# prosthesis.net
KiCad netlist of a schematic drawn in Altium Designer
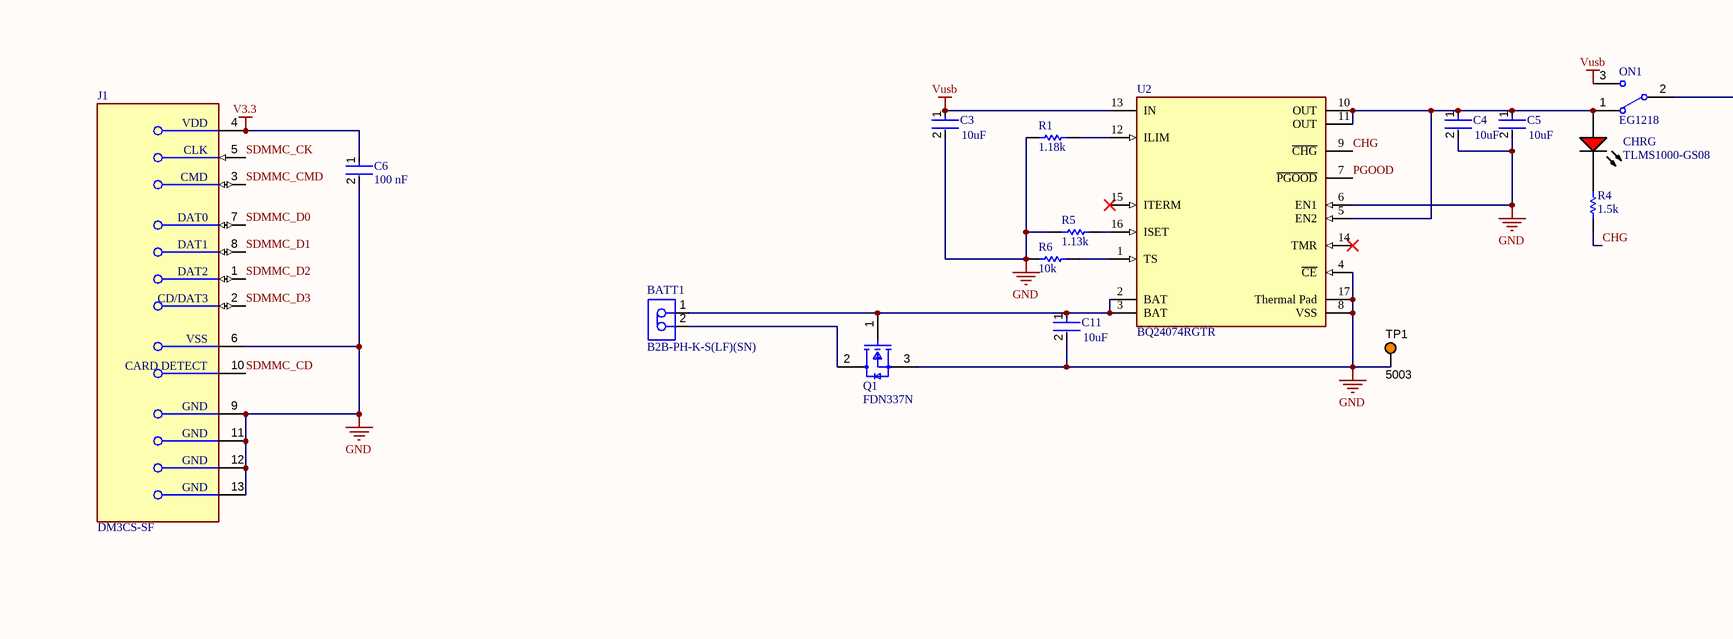
[diagram p0: prosthesis.SchDoc, top left]
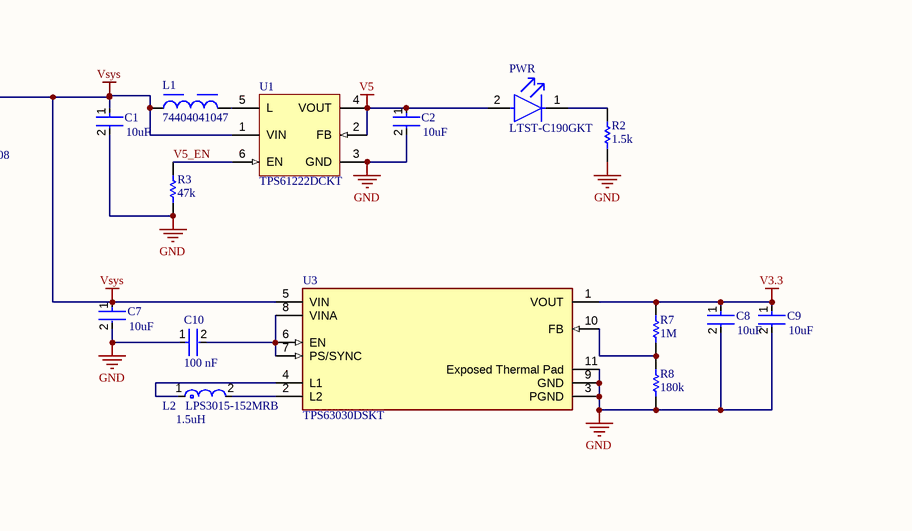
[diagram p1: prosthesis.SchDoc, top right]
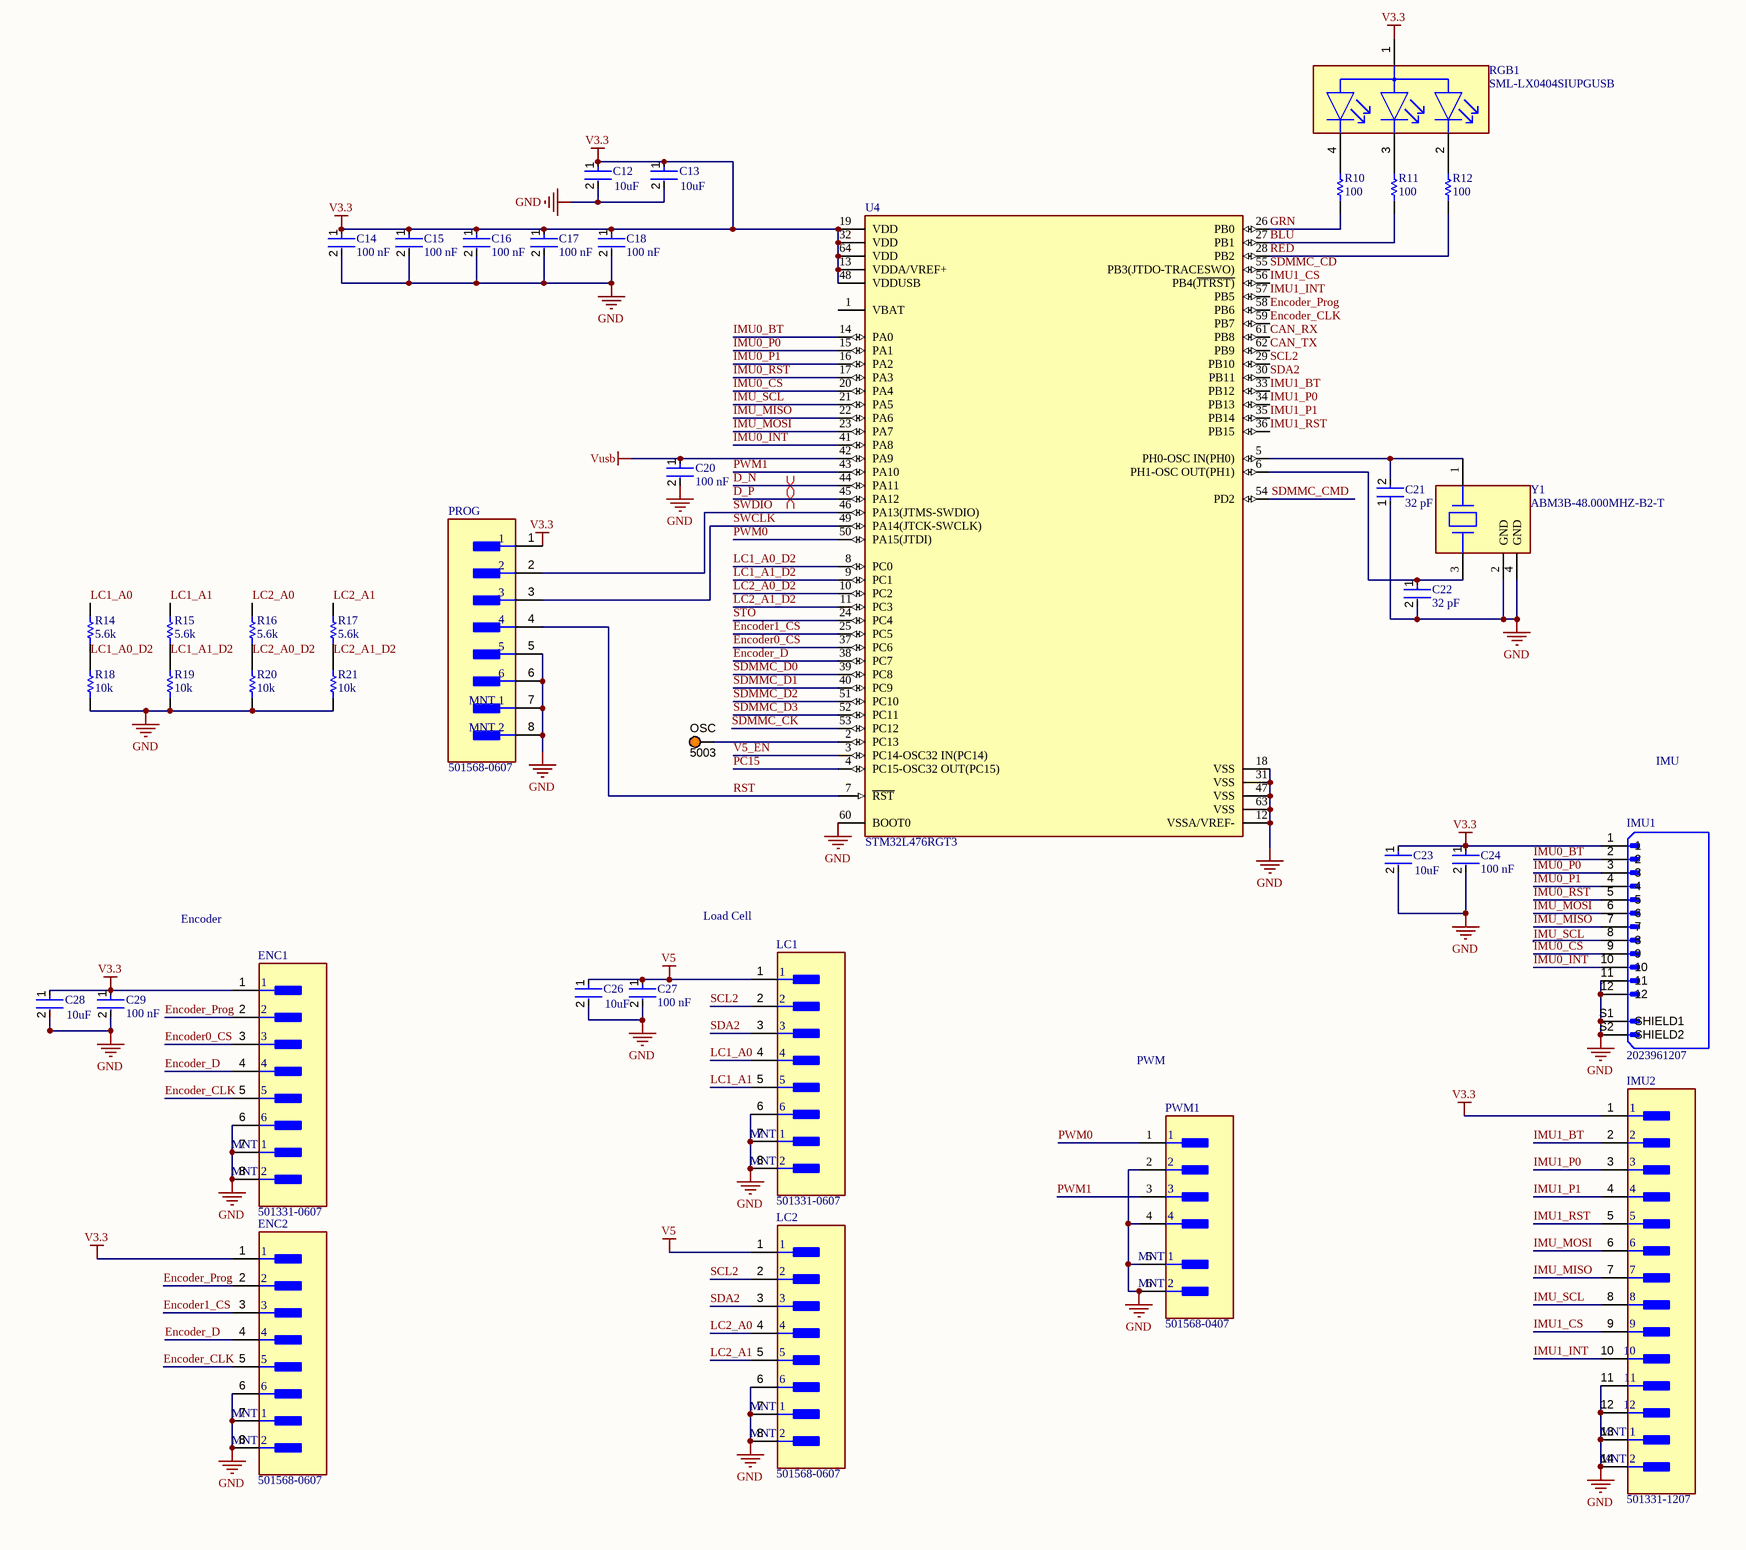
[diagram p2: prosthesis.SchDoc, bottom left]
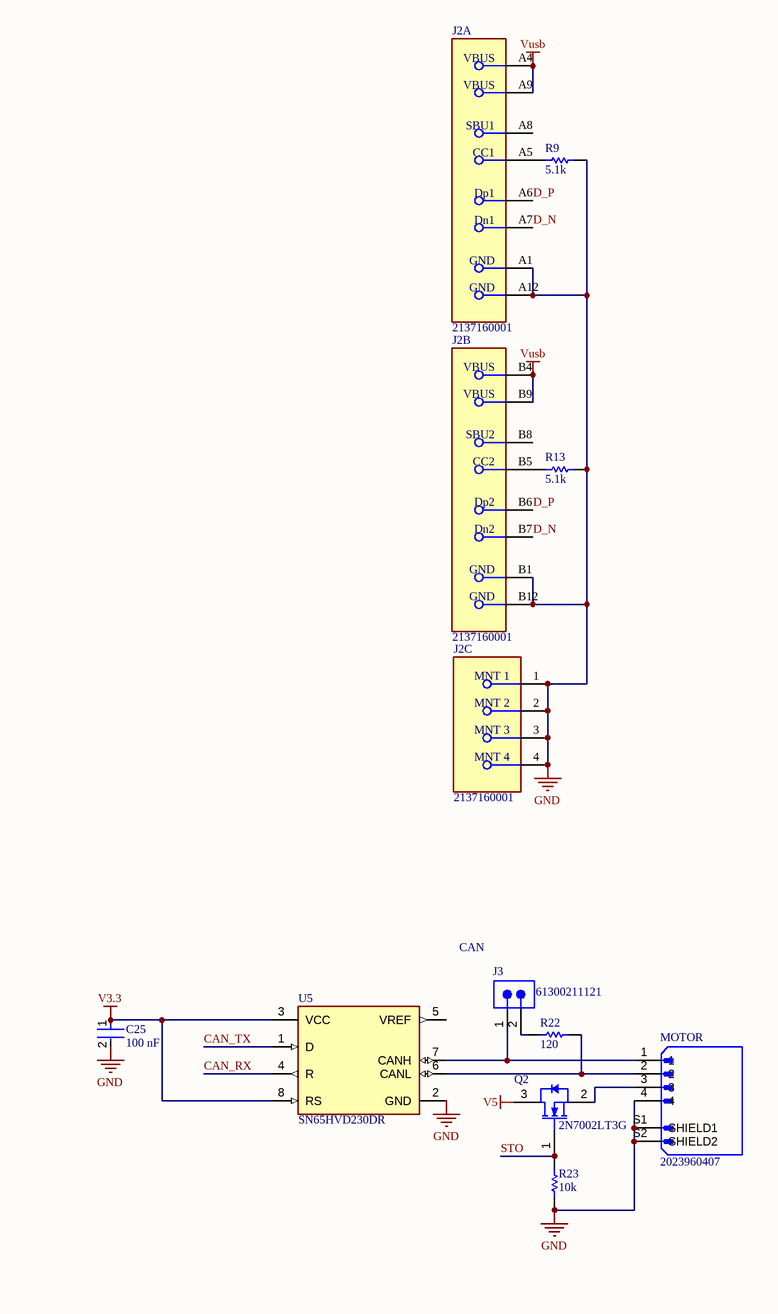
[diagram p3: prosthesis.SchDoc, bottom right]

(export (version "E")
  (design (tool "Eeschema 10.0.6"))
  (components
    (comp (ref "BATT1")
      (value "B2B-PH-K-S(LF)(SN)")
      (footprint "JST-B2B-PH-K-S_V")
      (fields (field (name "MANUFACTURER") "JST"))
      (libsource (lib "Altium Content Vault") (part "CN-2P-F-QF2"))
    )
    (comp (ref "C1")
      (value "GRM21BR61C106KE15L")
      (footprint "FP-GRM21B-0_1-IPC_C")
      (description "Chip Multilayer Ceramic Capacitors for General Purpose, 0805, 10uF, X5R, 15%, 10%, 16V")
      (fields
        (field (name "TOLERANCE") "10%")
        (field (name "VOLTAGE") "16V")
        (field (name "CAPACITANCE") "10uF")
      )
      (libsource (lib "Altium Content Vault") (part "b4654b650e69147ec39a6b967a45e02"))
    )
    (comp (ref "C2")
      (value "GRM21BR61C106KE15L")
      (footprint "FP-GRM21B-0_1-IPC_C")
      (description "Chip Multilayer Ceramic Capacitors for General Purpose, 0805, 10uF, X5R, 15%, 10%, 16V")
      (fields
        (field (name "TOLERANCE") "10%")
        (field (name "VOLTAGE") "16V")
        (field (name "CAPACITANCE") "10uF")
      )
      (libsource (lib "Altium Content Vault") (part "b4654b650e69147ec39a6b967a45e02"))
    )
    (comp (ref "C3")
      (value "GRM21BR61C106KE15L")
      (footprint "FP-GRM21B-0_1-IPC_C")
      (description "Chip Multilayer Ceramic Capacitors for General Purpose, 0805, 10uF, X5R, 15%, 10%, 16V")
      (fields
        (field (name "TOLERANCE") "10%")
        (field (name "VOLTAGE") "16V")
        (field (name "CAPACITANCE") "10uF")
      )
      (libsource (lib "Altium Content Vault") (part "b4654b650e69147ec39a6b967a45e02"))
    )
    (comp (ref "C4")
      (value "GRM21BR61C106KE15L")
      (footprint "FP-GRM21B-0_1-IPC_C")
      (description "Chip Multilayer Ceramic Capacitors for General Purpose, 0805, 10uF, X5R, 15%, 10%, 16V")
      (fields
        (field (name "TOLERANCE") "10%")
        (field (name "VOLTAGE") "16V")
        (field (name "CAPACITANCE") "10uF")
      )
      (libsource (lib "Altium Content Vault") (part "b4654b650e69147ec39a6b967a45e02"))
    )
    (comp (ref "C5")
      (value "GRM21BR61C106KE15L")
      (footprint "FP-GRM21B-0_1-IPC_C")
      (description "Chip Multilayer Ceramic Capacitors for General Purpose, 0805, 10uF, X5R, 15%, 10%, 16V")
      (fields
        (field (name "TOLERANCE") "10%")
        (field (name "VOLTAGE") "16V")
        (field (name "CAPACITANCE") "10uF")
      )
      (libsource (lib "Altium Content Vault") (part "b4654b650e69147ec39a6b967a45e02"))
    )
    (comp (ref "C6")
      (value "100 nF")
      (footprint "FP-CC0805-0_85-MFG")
      (description "CAP CER 0.1UF 16V X7R 0805")
      (fields
        (field (name "MANUFACTURER PART NUMBER") "CC0805KRX7R7BB104")
        (field (name "MANUFACTURER") "Yageo")
      )
      (libsource (lib "Altium Content Vault") (part "11868f565c42a9108669ba33697ecf6"))
    )
    (comp (ref "C7")
      (value "GRM21BR61C106KE15L")
      (footprint "FP-GRM21B-0_1-IPC_C")
      (description "Chip Multilayer Ceramic Capacitors for General Purpose, 0805, 10uF, X5R, 15%, 10%, 16V")
      (fields
        (field (name "TOLERANCE") "10%")
        (field (name "VOLTAGE") "16V")
        (field (name "CAPACITANCE") "10uF")
      )
      (libsource (lib "Altium Content Vault") (part "b4654b650e69147ec39a6b967a45e02"))
    )
    (comp (ref "C8")
      (value "GRM21BR61C106KE15L")
      (footprint "FP-GRM21B-0_1-IPC_C")
      (description "Chip Multilayer Ceramic Capacitors for General Purpose, 0805, 10uF, X5R, 15%, 10%, 16V")
      (fields
        (field (name "TOLERANCE") "10%")
        (field (name "VOLTAGE") "16V")
        (field (name "CAPACITANCE") "10uF")
      )
      (libsource (lib "Altium Content Vault") (part "b4654b650e69147ec39a6b967a45e02"))
    )
    (comp (ref "C9")
      (value "GRM21BR61C106KE15L")
      (footprint "FP-GRM21B-0_1-IPC_C")
      (description "Chip Multilayer Ceramic Capacitors for General Purpose, 0805, 10uF, X5R, 15%, 10%, 16V")
      (fields
        (field (name "TOLERANCE") "10%")
        (field (name "VOLTAGE") "16V")
        (field (name "CAPACITANCE") "10uF")
      )
      (libsource (lib "Altium Content Vault") (part "b4654b650e69147ec39a6b967a45e02"))
    )
    (comp (ref "C10")
      (value "100 nF")
      (footprint "FP-CC0805-0_85-MFG")
      (description "CAP CER 0.1UF 16V X7R 0805")
      (fields
        (field (name "MANUFACTURER PART NUMBER") "CC0805KRX7R7BB104")
        (field (name "MANUFACTURER") "Yageo")
      )
      (libsource (lib "Altium Content Vault") (part "11868f565c42a9108669ba33697ecf6"))
    )
    (comp (ref "C11")
      (value "GRM21BR61C106KE15L")
      (footprint "FP-GRM21B-0_1-IPC_C")
      (description "Chip Multilayer Ceramic Capacitors for General Purpose, 0805, 10uF, X5R, 15%, 10%, 16V")
      (fields
        (field (name "TOLERANCE") "10%")
        (field (name "VOLTAGE") "16V")
        (field (name "CAPACITANCE") "10uF")
      )
      (libsource (lib "Altium Content Vault") (part "b4654b650e69147ec39a6b967a45e02"))
    )
    (comp (ref "C12")
      (value "GRM21BR61C106KE15L")
      (footprint "FP-GRM21B-0_1-IPC_C")
      (description "Chip Multilayer Ceramic Capacitors for General Purpose, 0805, 10uF, X5R, 15%, 10%, 16V")
      (fields
        (field (name "TOLERANCE") "10%")
        (field (name "VOLTAGE") "16V")
        (field (name "CAPACITANCE") "10uF")
      )
      (libsource (lib "Altium Content Vault") (part "b4654b650e69147ec39a6b967a45e02"))
    )
    (comp (ref "C13")
      (value "GRM21BR61C106KE15L")
      (footprint "FP-GRM21B-0_1-IPC_C")
      (description "Chip Multilayer Ceramic Capacitors for General Purpose, 0805, 10uF, X5R, 15%, 10%, 16V")
      (fields
        (field (name "TOLERANCE") "10%")
        (field (name "VOLTAGE") "16V")
        (field (name "CAPACITANCE") "10uF")
      )
      (libsource (lib "Altium Content Vault") (part "b4654b650e69147ec39a6b967a45e02"))
    )
    (comp (ref "C14")
      (value "100 nF")
      (footprint "FP-CC0805-0_85-MFG")
      (description "CAP CER 0.1UF 16V X7R 0805")
      (fields
        (field (name "MANUFACTURER PART NUMBER") "CC0805KRX7R7BB104")
        (field (name "MANUFACTURER") "Yageo")
      )
      (libsource (lib "Altium Content Vault") (part "11868f565c42a9108669ba33697ecf6"))
    )
    (comp (ref "C15")
      (value "100 nF")
      (footprint "FP-CC0805-0_85-MFG")
      (description "CAP CER 0.1UF 16V X7R 0805")
      (fields
        (field (name "MANUFACTURER PART NUMBER") "CC0805KRX7R7BB104")
        (field (name "MANUFACTURER") "Yageo")
      )
      (libsource (lib "Altium Content Vault") (part "11868f565c42a9108669ba33697ecf6"))
    )
    (comp (ref "C16")
      (value "100 nF")
      (footprint "FP-CC0805-0_85-MFG")
      (description "CAP CER 0.1UF 16V X7R 0805")
      (fields
        (field (name "MANUFACTURER PART NUMBER") "CC0805KRX7R7BB104")
        (field (name "MANUFACTURER") "Yageo")
      )
      (libsource (lib "Altium Content Vault") (part "11868f565c42a9108669ba33697ecf6"))
    )
    (comp (ref "C17")
      (value "100 nF")
      (footprint "FP-CC0805-0_85-MFG")
      (description "CAP CER 0.1UF 16V X7R 0805")
      (fields
        (field (name "MANUFACTURER PART NUMBER") "CC0805KRX7R7BB104")
        (field (name "MANUFACTURER") "Yageo")
      )
      (libsource (lib "Altium Content Vault") (part "11868f565c42a9108669ba33697ecf6"))
    )
    (comp (ref "C18")
      (value "100 nF")
      (footprint "FP-CC0805-0_85-MFG")
      (description "CAP CER 0.1UF 16V X7R 0805")
      (fields
        (field (name "MANUFACTURER PART NUMBER") "CC0805KRX7R7BB104")
        (field (name "MANUFACTURER") "Yageo")
      )
      (libsource (lib "Altium Content Vault") (part "11868f565c42a9108669ba33697ecf6"))
    )
    (comp (ref "C20")
      (value "100 nF")
      (footprint "FP-CC0805-0_85-MFG")
      (description "CAP CER 0.1UF 16V X7R 0805")
      (fields
        (field (name "MANUFACTURER PART NUMBER") "CC0805KRX7R7BB104")
        (field (name "MANUFACTURER") "Yageo")
      )
      (libsource (lib "Altium Content Vault") (part "11868f565c42a9108669ba33697ecf6"))
    )
    (comp (ref "C21")
      (value "32 pF")
      (footprint "FP-CC0805-0_85-MFG")
      (description "CAP CER 32pF 16V X7R 0805")
      (fields
        (field (name "MANUFACTURER PART NUMBER") "CC0805KRX7R7BB104")
        (field (name "MANUFACTURER") "Yageo")
      )
      (libsource (lib "Altium Content Vault") (part "11868f565c42a9108669ba33697ecf6"))
    )
    (comp (ref "C22")
      (value "32 pF")
      (footprint "FP-CC0805-0_85-MFG")
      (description "CAP CER 32pF 16V X7R 0805")
      (fields
        (field (name "MANUFACTURER PART NUMBER") "CC0805KRX7R7BB104")
        (field (name "MANUFACTURER") "Yageo")
      )
      (libsource (lib "Altium Content Vault") (part "11868f565c42a9108669ba33697ecf6"))
    )
    (comp (ref "C23")
      (value "GRM21BR61C106KE15L")
      (footprint "FP-GRM21B-0_1-IPC_C")
      (description "Chip Multilayer Ceramic Capacitors for General Purpose, 0805, 10uF, X5R, 15%, 10%, 16V")
      (fields
        (field (name "TOLERANCE") "10%")
        (field (name "VOLTAGE") "16V")
        (field (name "CAPACITANCE") "10uF")
      )
      (libsource (lib "Altium Content Vault") (part "b4654b650e69147ec39a6b967a45e02"))
    )
    (comp (ref "C24")
      (value "100 nF")
      (footprint "FP-CC0805-0_85-MFG")
      (description "CAP CER 0.1UF 16V X7R 0805")
      (fields
        (field (name "MANUFACTURER PART NUMBER") "CC0805KRX7R7BB104")
        (field (name "MANUFACTURER") "Yageo")
      )
      (libsource (lib "Altium Content Vault") (part "11868f565c42a9108669ba33697ecf6"))
    )
    (comp (ref "C25")
      (value "100 nF")
      (footprint "FP-CC0805-0_85-MFG")
      (description "CAP CER 0.1UF 16V X7R 0805")
      (fields
        (field (name "MANUFACTURER PART NUMBER") "CC0805KRX7R7BB104")
        (field (name "MANUFACTURER") "Yageo")
      )
      (libsource (lib "Altium Content Vault") (part "11868f565c42a9108669ba33697ecf6"))
    )
    (comp (ref "C26")
      (value "GRM21BR61C106KE15L")
      (footprint "FP-GRM21B-0_1-IPC_C")
      (description "Chip Multilayer Ceramic Capacitors for General Purpose, 0805, 10uF, X5R, 15%, 10%, 16V")
      (fields
        (field (name "TOLERANCE") "10%")
        (field (name "VOLTAGE") "16V")
        (field (name "CAPACITANCE") "10uF")
      )
      (libsource (lib "Altium Content Vault") (part "b4654b650e69147ec39a6b967a45e02"))
    )
    (comp (ref "C27")
      (value "100 nF")
      (footprint "FP-CC0805-0_85-MFG")
      (description "CAP CER 0.1UF 16V X7R 0805")
      (fields
        (field (name "MANUFACTURER PART NUMBER") "CC0805KRX7R7BB104")
        (field (name "MANUFACTURER") "Yageo")
      )
      (libsource (lib "Altium Content Vault") (part "11868f565c42a9108669ba33697ecf6"))
    )
    (comp (ref "C28")
      (value "GRM21BR61C106KE15L")
      (footprint "FP-GRM21B-0_1-IPC_C")
      (description "Chip Multilayer Ceramic Capacitors for General Purpose, 0805, 10uF, X5R, 15%, 10%, 16V")
      (fields
        (field (name "TOLERANCE") "10%")
        (field (name "VOLTAGE") "16V")
        (field (name "CAPACITANCE") "10uF")
      )
      (libsource (lib "Altium Content Vault") (part "b4654b650e69147ec39a6b967a45e02"))
    )
    (comp (ref "C29")
      (value "100 nF")
      (footprint "FP-CC0805-0_85-MFG")
      (description "CAP CER 0.1UF 16V X7R 0805")
      (fields
        (field (name "MANUFACTURER PART NUMBER") "CC0805KRX7R7BB104")
        (field (name "MANUFACTURER") "Yageo")
      )
      (libsource (lib "Altium Content Vault") (part "11868f565c42a9108669ba33697ecf6"))
    )
    (comp (ref "CHRG")
      (value "TLMS1000-GS08")
      (footprint "VISH-TLMS1000_V")
      (description "Low Current LED, 40 mW, 1.8 V, -40 to 100 degC, 2-Pin SMD (0603), RoHS, Tape and Reel")
      (fields (field (name "MANUFACTURER") "Vishay"))
      (libsource (lib "Altium Content Vault") (part "LED-RED-AK-2"))
    )
    (comp (ref "ENC1")
      (value "501331-0607")
      (footprint "FP-501331-0607-MFG")
      (description "CONN HEADER SMD 6POS 1MM")
      (libsource (lib "Altium Content Vault") (part "2bd7785e6f3406c6201afa29ba70f07"))
    )
    (comp (ref "ENC2")
      (value "501568-0607")
      (footprint "FP-501568-0607-MFG")
      (description "CONN HEADER SMD R/A 6POS 1MM")
      (fields
        (field (name "MANUFACTURER") "Molex")
        (field (name "OCTOPART") "https://octopart.com/501568-0607-molex-1389391")
      )
      (libsource (lib "") (part "1b394f14087da03cce32c17bd8f6206_1"))
    )
    (comp (ref "IMU1")
      (value "2023961207")
      (footprint "MOLEX_2023961207")
      (libsource (lib "2023961207") (part "2023961207"))
    )
    (comp (ref "IMU2")
      (value "501331-1207")
      (footprint "FP-501331-1207-MFG")
      (description "CONN HEADER SMD 12POS 1MM")
      (libsource (lib "Altium Content Vault") (part "17576ad8f6f7a90bfd1824352d618be"))
    )
    (comp (ref "J1")
      (value "DM3CS-SF")
      (footprint "FP-DM3CS-SF-MFG")
      (description "CONN MICRO SD CARD HINGED TYPE")
      (libsource (lib "Altium Content Vault") (part "bac915de5305cfdd1ca301aae530106"))
    )
    (comp (ref "J2")
      (value "2137160001")
      (footprint "FP-2137160001-MFG")
      (description "2137160001 Conn USB 2.0 Type C F 16 POS 0.85mm Solder RA Thru-Hole 16 Terminal 1 Port T/R")
      (libsource (lib "Altium Content Vault") (part "b696ed38c1c45f0dfa1e84b6b439290"))
    )
    (comp (ref "J3")
      (value "61300211121")
      (footprint "61300211121")
      (libsource (lib "Altium Content Vault") (part "Header_Male_1R_02P"))
    )
    (comp (ref "L1")
      (value "74404041047")
      (footprint "WE-LQS_4012")
      (description "74404041047 Inductors, Fixed, WE-LQS SMD 4012 4.7uH 1.55A 91mOhms")
      (fields (field (name "TOLERANCE") "20%"))
      (libsource (lib "Altium Content Vault") (part "Inductor - 3"))
    )
    (comp (ref "L2")
      (value "LPS3015-152MRB")
      (footprint "FP-LPS3015-MFG")
      (description "Fixed Inductors LPS3015 AEC-Q200 1.5uH 1.4A 20% SMD")
      (fields (field (name "INDUCTANCE") "1.5uH") (field (name "TOLERANCE") "20%"))
      (libsource (lib "Altium Content Vault") (part "4cc4b267dca4c8e51f7102f422741d8"))
    )
    (comp (ref "LC1")
      (value "501331-0607")
      (footprint "FP-501331-0607-MFG")
      (description "CONN HEADER SMD 6POS 1MM")
      (libsource (lib "Altium Content Vault") (part "2bd7785e6f3406c6201afa29ba70f07"))
    )
    (comp (ref "LC2")
      (value "501568-0607")
      (footprint "FP-501568-0607-MFG")
      (description "CONN HEADER SMD R/A 6POS 1MM")
      (fields
        (field (name "MANUFACTURER") "Molex")
        (field (name "OCTOPART") "https://octopart.com/501568-0607-molex-1389391")
      )
      (libsource (lib "") (part "1b394f14087da03cce32c17bd8f6206_1"))
    )
    (comp (ref "MOTOR")
      (value "2023960407")
      (footprint "MOLEX_2023960407")
      (libsource (lib "2023960407") (part "2023960407"))
    )
    (comp (ref "ON1")
      (value "EG1218")
      (footprint "ESWI-EG1218_V")
      (description "Slide Switch, 500 V, -20 to 70 degC, 3-Pin THD, RoHS")
      (libsource (lib "Altium Content Vault") (part "SW-SPDT-3_B"))
    )
    (comp (ref "OSC")
      (value "5003")
      (footprint "KSTN-5003")
      (description "Test Point, Orange, 1-Pin THD, RoHS")
      (libsource (lib "Altium Content Vault") (part "TESTPOINT_ORANGE"))
    )
    (comp (ref "PROG")
      (value "501568-0607")
      (footprint "FP-501568-0607-MFG")
      (description "CONN HEADER SMD R/A 6POS 1MM")
      (fields
        (field (name "MANUFACTURER") "Molex")
        (field (name "OCTOPART") "https://octopart.com/501568-0607-molex-1389391")
      )
      (libsource (lib "Altium Content Vault") (part "1b394f14087da03cce32c17bd8f6206"))
    )
    (comp (ref "PWM1")
      (value "501568-0407")
      (footprint "FP-501568-0407-MFG")
      (description "CONN HEADER SMD R/A 4POS 1MM")
      (libsource (lib "Altium Content Vault") (part "9ad138ae26d927171cc05ac156b0a09"))
    )
    (comp (ref "PWR")
      (value "LTST-C190GKT")
      (footprint "FP-LTST-C190GKT-MFG")
      (description "LED GREEN CLEAR CHIP SMD")
      (fields (field (name "VOLTAGE") "2V"))
      (libsource (lib "Altium Content Vault") (part "8706943c75ba83719d021d2fdc84c58"))
    )
    (comp (ref "Q1")
      (value "FDN337N")
      (footprint "FP-527AG-MFG")
      (description "MOSFET N-CH 30V 2.2A SSOT3")
      (libsource (lib "Altium Content Vault") (part "b44c8776e10362b01251f5cff19d373"))
    )
    (comp (ref "Q2")
      (value "2N7002LT3G")
      (footprint "ONSC-SOT-23-3-318-08_V")
      (description "Small Signal MOSFET, 60 V, 115 mA, N-Channel, 3-Pin SOT-23, Pb-Free, Tape and Reel")
      (fields (field (name "MANUFACTURER") "On Semiconductor"))
      (libsource (lib "Altium Content Vault") (part "ONSC-NMOS-G1S2D3-3"))
    )
    (comp (ref "R1")
      (value "1.18k")
      (footprint "RESC2013X70X40ML20T20")
      (fields (field (name "MANUFACTURER") "Panasonic") (field (name "PART NUMBER") "ERJ-6ENF1181V"))
      (libsource (lib "Altium Content Vault") (part "RES"))
    )
    (comp (ref "R2")
      (value "1.5k")
      (footprint "RESC2013X70X40NL20T20")
      (fields (field (name "MANUFACTURER") "Panasonic") (field (name "PART NUMBER") "ERJ-6GEYJ152V"))
      (libsource (lib "Altium Content Vault") (part "RES"))
    )
    (comp (ref "R3")
      (value "47k")
      (footprint "RESC2013X70X40ML20T20")
      (fields (field (name "MANUFACTURER") "Panasonic") (field (name "PART NUMBER") "ERJ-6GEYJ473V"))
      (libsource (lib "Altium Content Vault") (part "RES"))
    )
    (comp (ref "R4")
      (value "1.5k")
      (footprint "RESC2013X70X40NL20T20")
      (fields (field (name "MANUFACTURER") "Panasonic") (field (name "PART NUMBER") "ERJ-6GEYJ152V"))
      (libsource (lib "Altium Content Vault") (part "RES"))
    )
    (comp (ref "R5")
      (value "1.13k")
      (footprint "RESC2013X60X35NL10T20")
      (fields (field (name "MANUFACTURER") "Yageo") (field (name "PART NUMBER") "RC0805FR-071K13L"))
      (libsource (lib "Altium Content Vault") (part "RES"))
    )
    (comp (ref "R6")
      (value "10k")
      (footprint "RESC2013X60X35NL10T20")
      (description "Chip Resistor, 10 KOhm, +/- 1%, 0.125 W, -55 to 155 degC, 0805 (2012 Metric), RoHS, Tape and Reel")
      (fields (field (name "MANUFACTURER") "Yageo"))
      (libsource (lib "Altium Content Vault") (part "RES-2"))
    )
    (comp (ref "R7")
      (value "1M")
      (footprint "RESC1608X55X30NL15T15")
      (fields (field (name "PART NUMBER") "ERJ-3GEYJ105V") (field (name "MANUFACTURER") "Panasonic"))
      (libsource (lib "Altium Content Vault") (part "RES"))
    )
    (comp (ref "R8")
      (value "180k")
      (footprint "RESC2013X50X40NL20T20")
      (fields (field (name "PART NUMBER") "RG2012N-184-W-T1") (field (name "MANUFACTURER") "Susumu"))
      (libsource (lib "Altium Content Vault") (part "RES"))
    )
    (comp (ref "R9")
      (value "5.1k")
      (footprint "RESC2013X60X40LL20T25")
      (fields (field (name "MANUFACTURER") "Panasonic") (field (name "PART NUMBER") "ERA-6YEB512V"))
      (libsource (lib "Altium Content Vault") (part "RES"))
    )
    (comp (ref "R10")
      (value "100")
      (footprint "RESC2013X60X40ML20T25")
      (fields (field (name "MANUFACTURER") "Panasonic") (field (name "PART NUMBER") "ERA6AEB101V"))
      (libsource (lib "Altium Content Vault") (part "RES"))
    )
    (comp (ref "R11")
      (value "100")
      (footprint "RESC2013X60X40ML20T25")
      (fields (field (name "MANUFACTURER") "Panasonic") (field (name "PART NUMBER") "ERA6AEB101V"))
      (libsource (lib "Altium Content Vault") (part "RES"))
    )
    (comp (ref "R12")
      (value "100")
      (footprint "RESC2013X60X40ML20T25")
      (fields (field (name "MANUFACTURER") "Panasonic") (field (name "PART NUMBER") "ERA6AEB101V"))
      (libsource (lib "Altium Content Vault") (part "RES"))
    )
    (comp (ref "R13")
      (value "5.1k")
      (footprint "RESC2013X60X40LL20T25")
      (fields (field (name "MANUFACTURER") "Panasonic") (field (name "PART NUMBER") "ERA-6YEB512V"))
      (libsource (lib "Altium Content Vault") (part "RES"))
    )
    (comp (ref "R14")
      (value "5.6k")
      (footprint "RESC2013X70X40LL20T20")
      (fields (field (name "PART NUMBER") "ERJ6ENF5601V") (field (name "MANUFACTURER") "Panasonic"))
      (libsource (lib "Altium Content Vault") (part "RES"))
    )
    (comp (ref "R15")
      (value "5.6k")
      (footprint "RESC2013X70X40LL20T20")
      (fields (field (name "PART NUMBER") "ERJ6ENF5601V") (field (name "MANUFACTURER") "Panasonic"))
      (libsource (lib "Altium Content Vault") (part "RES"))
    )
    (comp (ref "R16")
      (value "5.6k")
      (footprint "RESC2013X70X40LL20T20")
      (fields (field (name "PART NUMBER") "ERJ6ENF5601V") (field (name "MANUFACTURER") "Panasonic"))
      (libsource (lib "Altium Content Vault") (part "RES"))
    )
    (comp (ref "R17")
      (value "5.6k")
      (footprint "RESC2013X70X40LL20T20")
      (fields (field (name "PART NUMBER") "ERJ6ENF5601V") (field (name "MANUFACTURER") "Panasonic"))
      (libsource (lib "Altium Content Vault") (part "RES"))
    )
    (comp (ref "R18")
      (value "10k")
      (footprint "RESC2013X70X40LL20T20")
      (fields (field (name "PART NUMBER") "ERJ6ENF5601V") (field (name "MANUFACTURER") "Panasonic"))
      (libsource (lib "Altium Content Vault") (part "RES"))
    )
    (comp (ref "R19")
      (value "10k")
      (footprint "RESC2013X70X40LL20T20")
      (fields (field (name "PART NUMBER") "ERJ6ENF5601V") (field (name "MANUFACTURER") "Panasonic"))
      (libsource (lib "Altium Content Vault") (part "RES"))
    )
    (comp (ref "R20")
      (value "10k")
      (footprint "RESC2013X70X40LL20T20")
      (fields (field (name "PART NUMBER") "ERJ6ENF5601V") (field (name "MANUFACTURER") "Panasonic"))
      (libsource (lib "Altium Content Vault") (part "RES"))
    )
    (comp (ref "R21")
      (value "10k")
      (footprint "RESC2013X70X40LL20T20")
      (fields (field (name "PART NUMBER") "ERJ6ENF5601V") (field (name "MANUFACTURER") "Panasonic"))
      (libsource (lib "Altium Content Vault") (part "RES"))
    )
    (comp (ref "R22")
      (value "120")
      (footprint "RESC2013X60X40ML20T25")
      (fields (field (name "MANUFACTURER") "Panasonic") (field (name "PART NUMBER") "ERA6AEB121V"))
      (libsource (lib "Altium Content Vault") (part "RES"))
    )
    (comp (ref "R23")
      (value "10k")
      (footprint "RESC2013X70X40LL20T20")
      (fields (field (name "PART NUMBER") "ERJ6ENF5601V") (field (name "MANUFACTURER") "Panasonic"))
      (libsource (lib "Altium Content Vault") (part "RES"))
    )
    (comp (ref "RGB1")
      (value "SML-LX0404SIUPGUSB")
      (footprint "FP-SML-LX0404SIUPGUSB-MFG")
      (description "LED RGB CLEAR SMD")
      (libsource (lib "Altium Content Vault") (part "2e8871f6955a40d35a6a753e53ead77"))
    )
    (comp (ref "TP1")
      (value "5003")
      (footprint "KSTN-5003")
      (description "Test Point, Orange, 1-Pin THD, RoHS")
      (libsource (lib "Altium Content Vault") (part "TESTPOINT_ORANGE"))
    )
    (comp (ref "U1")
      (value "TPS61222DCKT")
      (footprint "DCK0006A_N")
      (fields (field (name "MANUFACTURER") "Texas Instruments"))
      (libsource (lib "Altium Content Vault") (part "TI-TPS61222DCK6"))
    )
    (comp (ref "U2")
      (value "BQ24074RGTR")
      (footprint "FP-RGT0016C-IPC_B")
      (description "IC LI-ION CHARGE MGMT 16-QFN")
      (libsource (lib "Altium Content Vault") (part "bc0294d1c007ba64400ebcffad863a1"))
    )
    (comp (ref "U3")
      (value "TPS63030DSKT")
      (footprint "FP-DSK0010A-IPC_B")
      (description "IC REG BCK BST ADJ 900MA 10SON")
      (libsource (lib "Altium Content Vault") (part "ec107bf50e5dd765c8e465f0f6f2d96"))
    )
    (comp (ref "U4")
      (value "STM32L476RGT3")
      (footprint "FP-LQFP64-5W-IPC_C")
      (description "IC MCU 32BIT 1MB FLASH 64LQFP")
      (libsource (lib "Altium Content Vault") (part "74cda0a56cc221a62fcf3ef167a0dda"))
    )
    (comp (ref "U5")
      (value "SN65HVD230DR")
      (footprint "FP-D0008A-IPC_A")
      (description "IC TRANSCEIVER HALF 1/1 8SOIC")
      (libsource (lib "Altium Content Vault") (part "43b56812b1adf0e60a7acfb7c27ab91"))
    )
    (comp (ref "Y1")
      (value "ABM3B-48.000MHZ-B2-T")
      (footprint "FP-ABM3B-MFG")
      (description "Crystal 48MHz ±20ppm 18pF SMD-4 5mm x 3.2mm")
      (fields (field (name "TOLERANCE") "20ppm"))
      (libsource (lib "Altium Content Vault") (part "48e526d86b7f2615d98721063c72f49"))
    )
  )
  (nets
    (net (code "1") (name "/BLU") (class "Default")
      (node (ref "R11") (pin "1") (pinfunction "1_1") (pintype "passive"))
      (node (ref "U4") (pin "27") (pinfunction "PB1_27") (pintype "bidirectional"))
    )
    (net (code "2") (name "/CAN_RX") (class "Default")
      (node (ref "U4") (pin "61") (pinfunction "PB8_61") (pintype "bidirectional"))
      (node (ref "U5") (pin "4") (pinfunction "R_4") (pintype "output"))
    )
    (net (code "3") (name "/CAN_TX") (class "Default")
      (node (ref "U4") (pin "62") (pinfunction "PB9_62") (pintype "bidirectional"))
      (node (ref "U5") (pin "1") (pinfunction "D_1") (pintype "input"))
    )
    (net (code "4") (name "/CHG") (class "Default")
      (node (ref "R4") (pin "1") (pinfunction "1_1") (pintype "passive"))
      (node (ref "U2") (pin "9") (pinfunction "~{CHG}_9") (pintype "tri_state"))
    )
    (net (code "5") (name "/D_N") (class "Default")
      (node (ref "J2") (pin "A7") (pinfunction "Dn1_A7") (pintype "passive"))
      (node (ref "J2") (pin "B7") (pinfunction "Dn2_B7") (pintype "passive"))
      (node (ref "U4") (pin "44") (pinfunction "PA11_44") (pintype "bidirectional"))
    )
    (net (code "6") (name "/D_P") (class "Default")
      (node (ref "J2") (pin "A6") (pinfunction "Dp1_A6") (pintype "passive"))
      (node (ref "J2") (pin "B6") (pinfunction "Dp2_B6") (pintype "passive"))
      (node (ref "U4") (pin "45") (pinfunction "PA12_45") (pintype "bidirectional"))
    )
    (net (code "7") (name "/Encoder0_CS") (class "Default")
      (node (ref "ENC1") (pin "3") (pinfunction "3_3") (pintype "passive"))
      (node (ref "U4") (pin "37") (pinfunction "PC6_37") (pintype "bidirectional"))
    )
    (net (code "8") (name "/Encoder1_CS") (class "Default")
      (node (ref "ENC2") (pin "3") (pinfunction "3_3") (pintype "passive"))
      (node (ref "U4") (pin "25") (pinfunction "PC5_25") (pintype "bidirectional"))
    )
    (net (code "9") (name "/Encoder_CLK") (class "Default")
      (node (ref "ENC1") (pin "5") (pinfunction "5_5") (pintype "passive"))
      (node (ref "ENC2") (pin "5") (pinfunction "5_5") (pintype "passive"))
      (node (ref "U4") (pin "59") (pinfunction "PB7_59") (pintype "bidirectional"))
    )
    (net (code "10") (name "/Encoder_D") (class "Default")
      (node (ref "ENC1") (pin "4") (pinfunction "4_4") (pintype "passive"))
      (node (ref "ENC2") (pin "4") (pinfunction "4_4") (pintype "passive"))
      (node (ref "U4") (pin "38") (pinfunction "PC7_38") (pintype "bidirectional"))
    )
    (net (code "11") (name "/Encoder_Prog") (class "Default")
      (node (ref "ENC1") (pin "2") (pinfunction "2_2") (pintype "passive"))
      (node (ref "ENC2") (pin "2") (pinfunction "2_2") (pintype "passive"))
      (node (ref "U4") (pin "58") (pinfunction "PB6_58") (pintype "bidirectional"))
    )
    (net (code "12") (name "/GRN") (class "Default")
      (node (ref "R10") (pin "1") (pinfunction "1_1") (pintype "passive"))
      (node (ref "U4") (pin "26") (pinfunction "PB0_26") (pintype "bidirectional"))
    )
    (net (code "13") (name "/IMU0_BT") (class "Default")
      (node (ref "IMU1") (pin "2") (pinfunction "2_2") (pintype "passive"))
      (node (ref "U4") (pin "14") (pinfunction "PA0_14") (pintype "bidirectional"))
    )
    (net (code "14") (name "/IMU0_CS") (class "Default")
      (node (ref "IMU1") (pin "9") (pinfunction "9_9") (pintype "passive"))
      (node (ref "U4") (pin "20") (pinfunction "PA4_20") (pintype "bidirectional"))
    )
    (net (code "15") (name "/IMU0_INT") (class "Default")
      (node (ref "IMU1") (pin "10") (pinfunction "10_10") (pintype "passive"))
      (node (ref "U4") (pin "41") (pinfunction "PA8_41") (pintype "bidirectional"))
    )
    (net (code "16") (name "/IMU0_P0") (class "Default")
      (node (ref "IMU1") (pin "3") (pinfunction "3_3") (pintype "passive"))
      (node (ref "U4") (pin "15") (pinfunction "PA1_15") (pintype "bidirectional"))
    )
    (net (code "17") (name "/IMU0_P1") (class "Default")
      (node (ref "IMU1") (pin "4") (pinfunction "4_4") (pintype "passive"))
      (node (ref "U4") (pin "16") (pinfunction "PA2_16") (pintype "bidirectional"))
    )
    (net (code "18") (name "/IMU0_RST") (class "Default")
      (node (ref "IMU1") (pin "5") (pinfunction "5_5") (pintype "passive"))
      (node (ref "U4") (pin "17") (pinfunction "PA3_17") (pintype "bidirectional"))
    )
    (net (code "19") (name "/IMU1_BT") (class "Default")
      (node (ref "IMU2") (pin "2") (pinfunction "2_2") (pintype "passive"))
      (node (ref "U4") (pin "33") (pinfunction "PB12_33") (pintype "bidirectional"))
    )
    (net (code "20") (name "/IMU1_CS") (class "Default")
      (node (ref "IMU2") (pin "9") (pinfunction "9_9") (pintype "passive"))
      (node (ref "U4") (pin "56") (pinfunction "PB4(~{JTRST)}_56") (pintype "bidirectional"))
    )
    (net (code "21") (name "/IMU1_INT") (class "Default")
      (node (ref "IMU2") (pin "10") (pinfunction "10_10") (pintype "passive"))
      (node (ref "U4") (pin "57") (pinfunction "PB5_57") (pintype "bidirectional"))
    )
    (net (code "22") (name "/IMU1_P0") (class "Default")
      (node (ref "IMU2") (pin "3") (pinfunction "3_3") (pintype "passive"))
      (node (ref "U4") (pin "34") (pinfunction "PB13_34") (pintype "bidirectional"))
    )
    (net (code "23") (name "/IMU1_P1") (class "Default")
      (node (ref "IMU2") (pin "4") (pinfunction "4_4") (pintype "passive"))
      (node (ref "U4") (pin "35") (pinfunction "PB14_35") (pintype "bidirectional"))
    )
    (net (code "24") (name "/IMU1_RST") (class "Default")
      (node (ref "IMU2") (pin "5") (pinfunction "5_5") (pintype "passive"))
      (node (ref "U4") (pin "36") (pinfunction "PB15_36") (pintype "bidirectional"))
    )
    (net (code "25") (name "/IMU_MISO") (class "Default")
      (node (ref "IMU1") (pin "7") (pinfunction "7_7") (pintype "passive"))
      (node (ref "IMU2") (pin "7") (pinfunction "7_7") (pintype "passive"))
      (node (ref "U4") (pin "22") (pinfunction "PA6_22") (pintype "bidirectional"))
    )
    (net (code "26") (name "/IMU_MOSI") (class "Default")
      (node (ref "IMU1") (pin "6") (pinfunction "6_6") (pintype "passive"))
      (node (ref "IMU2") (pin "6") (pinfunction "6_6") (pintype "passive"))
      (node (ref "U4") (pin "23") (pinfunction "PA7_23") (pintype "bidirectional"))
    )
    (net (code "27") (name "/IMU_SCL") (class "Default")
      (node (ref "IMU1") (pin "8") (pinfunction "8_8") (pintype "passive"))
      (node (ref "IMU2") (pin "8") (pinfunction "8_8") (pintype "passive"))
      (node (ref "U4") (pin "21") (pinfunction "PA5_21") (pintype "bidirectional"))
    )
    (net (code "28") (name "/LC1_A0") (class "Default")
      (node (ref "LC1") (pin "4") (pinfunction "4_4") (pintype "passive"))
      (node (ref "R14") (pin "2") (pinfunction "2_2") (pintype "passive"))
    )
    (net (code "29") (name "/LC1_A0_D2") (class "Default")
      (node (ref "R14") (pin "1") (pinfunction "1_1") (pintype "passive"))
      (node (ref "R18") (pin "2") (pinfunction "2_2") (pintype "passive"))
      (node (ref "U4") (pin "8") (pinfunction "PC0_8") (pintype "bidirectional"))
    )
    (net (code "30") (name "/LC1_A1") (class "Default")
      (node (ref "LC1") (pin "5") (pinfunction "5_5") (pintype "passive"))
      (node (ref "R15") (pin "2") (pinfunction "2_2") (pintype "passive"))
    )
    (net (code "31") (name "/LC1_A1_D2") (class "Default")
      (node (ref "R15") (pin "1") (pinfunction "1_1") (pintype "passive"))
      (node (ref "R19") (pin "2") (pinfunction "2_2") (pintype "passive"))
      (node (ref "U4") (pin "9") (pinfunction "PC1_9") (pintype "bidirectional"))
    )
    (net (code "32") (name "/LC2_A0") (class "Default")
      (node (ref "LC2") (pin "4") (pinfunction "4_4") (pintype "passive"))
      (node (ref "R16") (pin "2") (pinfunction "2_2") (pintype "passive"))
    )
    (net (code "33") (name "/LC2_A0_D2") (class "Default")
      (node (ref "R16") (pin "1") (pinfunction "1_1") (pintype "passive"))
      (node (ref "R20") (pin "2") (pinfunction "2_2") (pintype "passive"))
      (node (ref "U4") (pin "10") (pinfunction "PC2_10") (pintype "bidirectional"))
    )
    (net (code "34") (name "/LC2_A1") (class "Default")
      (node (ref "LC2") (pin "5") (pinfunction "5_5") (pintype "passive"))
      (node (ref "R17") (pin "2") (pinfunction "2_2") (pintype "passive"))
    )
    (net (code "35") (name "/LC2_A1_D2") (class "Default")
      (node (ref "R17") (pin "1") (pinfunction "1_1") (pintype "passive"))
      (node (ref "R21") (pin "2") (pinfunction "2_2") (pintype "passive"))
      (node (ref "U4") (pin "11") (pinfunction "PC3_11") (pintype "bidirectional"))
    )
    (net (code "36") (name "/PC15") (class "Default")
      (node (ref "U4") (pin "4") (pinfunction "PC15-OSC32_OUT(PC15)_4") (pintype "bidirectional"))
    )
    (net (code "37") (name "/PGOOD") (class "Default")
      (node (ref "U2") (pin "7") (pinfunction "~{PGOOD}_7") (pintype "tri_state"))
    )
    (net (code "38") (name "/PWM0") (class "Default")
      (node (ref "PWM1") (pin "1") (pinfunction "1_1") (pintype "passive"))
      (node (ref "U4") (pin "50") (pinfunction "PA15(JTDI)_50") (pintype "bidirectional"))
    )
    (net (code "39") (name "/PWM1") (class "Default")
      (node (ref "PWM1") (pin "3") (pinfunction "3_3") (pintype "passive"))
      (node (ref "U4") (pin "43") (pinfunction "PA10_43") (pintype "bidirectional"))
    )
    (net (code "40") (name "/RED") (class "Default")
      (node (ref "R12") (pin "1") (pinfunction "1_1") (pintype "passive"))
      (node (ref "U4") (pin "28") (pinfunction "PB2_28") (pintype "bidirectional"))
    )
    (net (code "41") (name "/RST") (class "Default")
      (node (ref "PROG") (pin "4") (pinfunction "4_4") (pintype "passive"))
      (node (ref "U4") (pin "7") (pinfunction "~{RST}_7") (pintype "input"))
    )
    (net (code "42") (name "/SCL2") (class "Default")
      (node (ref "LC1") (pin "2") (pinfunction "2_2") (pintype "passive"))
      (node (ref "LC2") (pin "2") (pinfunction "2_2") (pintype "passive"))
      (node (ref "U4") (pin "29") (pinfunction "PB10_29") (pintype "bidirectional"))
    )
    (net (code "43") (name "/SDA2") (class "Default")
      (node (ref "LC1") (pin "3") (pinfunction "3_3") (pintype "passive"))
      (node (ref "LC2") (pin "3") (pinfunction "3_3") (pintype "passive"))
      (node (ref "U4") (pin "30") (pinfunction "PB11_30") (pintype "bidirectional"))
    )
    (net (code "44") (name "/SDMMC_CD") (class "Default")
      (node (ref "J1") (pin "10") (pinfunction "CARD_DETECT_10") (pintype "passive"))
      (node (ref "U4") (pin "55") (pinfunction "PB3(JTDO-TRACESWO)_55") (pintype "bidirectional"))
    )
    (net (code "45") (name "/SDMMC_CK") (class "Default")
      (node (ref "J1") (pin "5") (pinfunction "CLK_5") (pintype "input"))
      (node (ref "U4") (pin "53") (pinfunction "PC12_53") (pintype "bidirectional"))
    )
    (net (code "46") (name "/SDMMC_CMD") (class "Default")
      (node (ref "J1") (pin "3") (pinfunction "CMD_3") (pintype "bidirectional"))
      (node (ref "U4") (pin "54") (pinfunction "PD2_54") (pintype "bidirectional"))
    )
    (net (code "47") (name "/SDMMC_D0") (class "Default")
      (node (ref "J1") (pin "7") (pinfunction "DAT0_7") (pintype "bidirectional"))
      (node (ref "U4") (pin "39") (pinfunction "PC8_39") (pintype "bidirectional"))
    )
    (net (code "48") (name "/SDMMC_D1") (class "Default")
      (node (ref "J1") (pin "8") (pinfunction "DAT1_8") (pintype "bidirectional"))
      (node (ref "U4") (pin "40") (pinfunction "PC9_40") (pintype "bidirectional"))
    )
    (net (code "49") (name "/SDMMC_D2") (class "Default")
      (node (ref "J1") (pin "1") (pinfunction "DAT2_1") (pintype "bidirectional"))
      (node (ref "U4") (pin "51") (pinfunction "PC10_51") (pintype "bidirectional"))
    )
    (net (code "50") (name "/SDMMC_D3") (class "Default")
      (node (ref "J1") (pin "2") (pinfunction "CD/DAT3_2") (pintype "bidirectional"))
      (node (ref "U4") (pin "52") (pinfunction "PC11_52") (pintype "bidirectional"))
    )
    (net (code "51") (name "/STO") (class "Default")
      (node (ref "Q2") (pin "1") (pinfunction "G_1") (pintype "passive"))
      (node (ref "R23") (pin "2") (pinfunction "2_2") (pintype "passive"))
      (node (ref "U4") (pin "24") (pinfunction "PC4_24") (pintype "bidirectional"))
    )
    (net (code "52") (name "/SWCLK") (class "Default")
      (node (ref "PROG") (pin "3") (pinfunction "3_3") (pintype "passive"))
      (node (ref "U4") (pin "49") (pinfunction "PA14(JTCK-SWCLK)_49") (pintype "bidirectional"))
    )
    (net (code "53") (name "/SWDIO") (class "Default")
      (node (ref "PROG") (pin "2") (pinfunction "2_2") (pintype "passive"))
      (node (ref "U4") (pin "46") (pinfunction "PA13(JTMS-SWDIO)_46") (pintype "bidirectional"))
    )
    (net (code "54") (name "/V5_EN") (class "Default")
      (node (ref "R3") (pin "2") (pinfunction "2_2") (pintype "passive"))
      (node (ref "U1") (pin "6") (pinfunction "EN_6") (pintype "input"))
      (node (ref "U4") (pin "3") (pinfunction "PC14-OSC32_IN(PC14)_3") (pintype "bidirectional"))
    )
    (net (code "55") (name "GND") (class "Default")
      (node (ref "C1") (pin "2") (pinfunction "2_2") (pintype "passive"))
      (node (ref "C10") (pin "1") (pinfunction "1_1") (pintype "passive"))
      (node (ref "C11") (pin "2") (pinfunction "2_2") (pintype "passive"))
      (node (ref "C12") (pin "2") (pinfunction "2_2") (pintype "passive"))
      (node (ref "C13") (pin "2") (pinfunction "2_2") (pintype "passive"))
      (node (ref "C14") (pin "2") (pinfunction "2_2") (pintype "passive"))
      (node (ref "C15") (pin "2") (pinfunction "2_2") (pintype "passive"))
      (node (ref "C16") (pin "2") (pinfunction "2_2") (pintype "passive"))
      (node (ref "C17") (pin "2") (pinfunction "2_2") (pintype "passive"))
      (node (ref "C18") (pin "2") (pinfunction "2_2") (pintype "passive"))
      (node (ref "C2") (pin "2") (pinfunction "2_2") (pintype "passive"))
      (node (ref "C20") (pin "2") (pinfunction "2_2") (pintype "passive"))
      (node (ref "C21") (pin "1") (pinfunction "1_1") (pintype "passive"))
      (node (ref "C22") (pin "2") (pinfunction "2_2") (pintype "passive"))
      (node (ref "C23") (pin "2") (pinfunction "2_2") (pintype "passive"))
      (node (ref "C24") (pin "2") (pinfunction "2_2") (pintype "passive"))
      (node (ref "C25") (pin "2") (pinfunction "2_2") (pintype "passive"))
      (node (ref "C26") (pin "2") (pinfunction "2_2") (pintype "passive"))
      (node (ref "C27") (pin "2") (pinfunction "2_2") (pintype "passive"))
      (node (ref "C28") (pin "2") (pinfunction "2_2") (pintype "passive"))
      (node (ref "C29") (pin "2") (pinfunction "2_2") (pintype "passive"))
      (node (ref "C3") (pin "2") (pinfunction "2_2") (pintype "passive"))
      (node (ref "C4") (pin "2") (pinfunction "2_2") (pintype "passive"))
      (node (ref "C5") (pin "2") (pinfunction "2_2") (pintype "passive"))
      (node (ref "C6") (pin "2") (pinfunction "2_2") (pintype "passive"))
      (node (ref "C7") (pin "2") (pinfunction "2_2") (pintype "passive"))
      (node (ref "C8") (pin "2") (pinfunction "2_2") (pintype "passive"))
      (node (ref "C9") (pin "2") (pinfunction "2_2") (pintype "passive"))
      (node (ref "ENC1") (pin "6") (pinfunction "6_6") (pintype "passive"))
      (node (ref "ENC1") (pin "7") (pinfunction "MNT_1_7") (pintype "passive"))
      (node (ref "ENC1") (pin "8") (pinfunction "MNT_2_8") (pintype "passive"))
      (node (ref "ENC2") (pin "6") (pinfunction "6_6") (pintype "passive"))
      (node (ref "ENC2") (pin "7") (pinfunction "MNT_1_7") (pintype "passive"))
      (node (ref "ENC2") (pin "8") (pinfunction "MNT_2_8") (pintype "passive"))
      (node (ref "IMU1") (pin "11") (pinfunction "11_11") (pintype "passive"))
      (node (ref "IMU1") (pin "12") (pinfunction "12_12") (pintype "passive"))
      (node (ref "IMU1") (pin "S1") (pinfunction "SHIELD1_S1") (pintype "passive"))
      (node (ref "IMU1") (pin "S2") (pinfunction "SHIELD2_S2") (pintype "passive"))
      (node (ref "IMU2") (pin "11") (pinfunction "11_11") (pintype "passive"))
      (node (ref "IMU2") (pin "12") (pinfunction "12_12") (pintype "passive"))
      (node (ref "IMU2") (pin "13") (pinfunction "MNT_1_13") (pintype "passive"))
      (node (ref "IMU2") (pin "14") (pinfunction "MNT_2_14") (pintype "passive"))
      (node (ref "J1") (pin "11") (pinfunction "GND_11") (pintype "power_in"))
      (node (ref "J1") (pin "12") (pinfunction "GND_12") (pintype "power_in"))
      (node (ref "J1") (pin "13") (pinfunction "GND_13") (pintype "power_in"))
      (node (ref "J1") (pin "6") (pinfunction "VSS_6") (pintype "power_in"))
      (node (ref "J1") (pin "9") (pinfunction "GND_9") (pintype "power_in"))
      (node (ref "J2") (pin "1") (pinfunction "MNT_1_1") (pintype "passive"))
      (node (ref "J2") (pin "2") (pinfunction "MNT_2_2") (pintype "passive"))
      (node (ref "J2") (pin "3") (pinfunction "MNT_3_3") (pintype "passive"))
      (node (ref "J2") (pin "4") (pinfunction "MNT_4_4") (pintype "passive"))
      (node (ref "J2") (pin "A1") (pinfunction "GND_A1") (pintype "passive"))
      (node (ref "J2") (pin "A12") (pinfunction "GND_A12") (pintype "passive"))
      (node (ref "J2") (pin "B1") (pinfunction "GND_B1") (pintype "passive"))
      (node (ref "J2") (pin "B12") (pinfunction "GND_B12") (pintype "passive"))
      (node (ref "LC1") (pin "6") (pinfunction "6_6") (pintype "passive"))
      (node (ref "LC1") (pin "7") (pinfunction "MNT_1_7") (pintype "passive"))
      (node (ref "LC1") (pin "8") (pinfunction "MNT_2_8") (pintype "passive"))
      (node (ref "LC2") (pin "6") (pinfunction "6_6") (pintype "passive"))
      (node (ref "LC2") (pin "7") (pinfunction "MNT_1_7") (pintype "passive"))
      (node (ref "LC2") (pin "8") (pinfunction "MNT_2_8") (pintype "passive"))
      (node (ref "MOTOR") (pin "4") (pinfunction "4_4") (pintype "passive"))
      (node (ref "MOTOR") (pin "S1") (pinfunction "SHIELD1_S1") (pintype "passive"))
      (node (ref "MOTOR") (pin "S2") (pinfunction "SHIELD2_S2") (pintype "passive"))
      (node (ref "PROG") (pin "5") (pinfunction "5_5") (pintype "passive"))
      (node (ref "PROG") (pin "6") (pinfunction "6_6") (pintype "passive"))
      (node (ref "PROG") (pin "7") (pinfunction "MNT_1_7") (pintype "passive"))
      (node (ref "PROG") (pin "8") (pinfunction "MNT_2_8") (pintype "passive"))
      (node (ref "PWM1") (pin "2") (pinfunction "2_2") (pintype "passive"))
      (node (ref "PWM1") (pin "4") (pinfunction "4_4") (pintype "passive"))
      (node (ref "PWM1") (pin "5") (pinfunction "MNT_1_5") (pintype "passive"))
      (node (ref "PWM1") (pin "6") (pinfunction "MNT_2_6") (pintype "passive"))
      (node (ref "Q1") (pin "3") (pinfunction "S_3") (pintype "passive"))
      (node (ref "R1") (pin "2") (pinfunction "2_2") (pintype "passive"))
      (node (ref "R13") (pin "2") (pinfunction "2_2") (pintype "passive"))
      (node (ref "R18") (pin "1") (pinfunction "1_1") (pintype "passive"))
      (node (ref "R19") (pin "1") (pinfunction "1_1") (pintype "passive"))
      (node (ref "R2") (pin "1") (pinfunction "1_1") (pintype "passive"))
      (node (ref "R20") (pin "1") (pinfunction "1_1") (pintype "passive"))
      (node (ref "R21") (pin "1") (pinfunction "1_1") (pintype "passive"))
      (node (ref "R23") (pin "1") (pinfunction "1_1") (pintype "passive"))
      (node (ref "R3") (pin "1") (pinfunction "1_1") (pintype "passive"))
      (node (ref "R5") (pin "1") (pinfunction "1_1") (pintype "passive"))
      (node (ref "R6") (pin "1") (pinfunction "1_1") (pintype "passive"))
      (node (ref "R8") (pin "1") (pinfunction "1_1") (pintype "passive"))
      (node (ref "R9") (pin "2") (pinfunction "2_2") (pintype "passive"))
      (node (ref "TP1") (pin "1") (pinfunction "1_1") (pintype "passive"))
      (node (ref "U1") (pin "3") (pinfunction "GND_3") (pintype "power_in"))
      (node (ref "U2") (pin "17") (pinfunction "Thermal_Pad_17") (pintype "power_in"))
      (node (ref "U2") (pin "4") (pinfunction "~{CE}_4") (pintype "input"))
      (node (ref "U2") (pin "6") (pinfunction "EN1_6") (pintype "input"))
      (node (ref "U2") (pin "8") (pinfunction "VSS_8") (pintype "power_in"))
      (node (ref "U3") (pin "11") (pinfunction "Exposed_Thermal_Pad_11") (pintype "power_in"))
      (node (ref "U3") (pin "3") (pinfunction "PGND_3") (pintype "power_in"))
      (node (ref "U3") (pin "9") (pinfunction "GND_9") (pintype "power_in"))
      (node (ref "U4") (pin "12") (pinfunction "VSSA/VREF-_12") (pintype "power_in"))
      (node (ref "U4") (pin "18") (pinfunction "VSS_18") (pintype "power_in"))
      (node (ref "U4") (pin "31") (pinfunction "VSS_31") (pintype "power_in"))
      (node (ref "U4") (pin "47") (pinfunction "VSS_47") (pintype "power_in"))
      (node (ref "U4") (pin "60") (pinfunction "BOOT0_60") (pintype "passive"))
      (node (ref "U4") (pin "63") (pinfunction "VSS_63") (pintype "power_in"))
      (node (ref "U5") (pin "2") (pinfunction "GND_2") (pintype "power_in"))
      (node (ref "Y1") (pin "2") (pinfunction "GND_2") (pintype "power_in"))
      (node (ref "Y1") (pin "4") (pinfunction "GND_4") (pintype "power_in"))
    )
    (net (code "56") (name "Net-(CHRG-A)") (class "Default")
      (node (ref "C4") (pin "1") (pinfunction "1_1") (pintype "passive"))
      (node (ref "C5") (pin "1") (pinfunction "1_1") (pintype "passive"))
      (node (ref "CHRG") (pin "1") (pinfunction "A_1") (pintype "passive"))
      (node (ref "ON1") (pin "1") (pinfunction "1_1") (pintype "passive"))
      (node (ref "U2") (pin "10") (pinfunction "OUT_10") (pintype "power_in"))
      (node (ref "U2") (pin "11") (pinfunction "OUT_11") (pintype "power_in"))
      (node (ref "U2") (pin "5") (pinfunction "EN2_5") (pintype "input"))
    )
    (net (code "57") (name "Net-(CHRG-K)") (class "Default")
      (node (ref "CHRG") (pin "2") (pinfunction "K_2") (pintype "passive"))
      (node (ref "R4") (pin "2") (pinfunction "2_2") (pintype "passive"))
    )
    (net (code "58") (name "Net-(J2A-CC1)") (class "Default")
      (node (ref "J2") (pin "A5") (pinfunction "CC1_A5") (pintype "passive"))
      (node (ref "R9") (pin "1") (pinfunction "1_1") (pintype "passive"))
    )
    (net (code "59") (name "Net-(J2B-CC2)") (class "Default")
      (node (ref "J2") (pin "B5") (pinfunction "CC2_B5") (pintype "passive"))
      (node (ref "R13") (pin "1") (pinfunction "1_1") (pintype "passive"))
    )
    (net (code "60") (name "Net-(J3-Pad2)") (class "Default")
      (node (ref "J3") (pin "2") (pinfunction "2_2") (pintype "passive"))
      (node (ref "R22") (pin "1") (pinfunction "1_1") (pintype "passive"))
    )
    (net (code "61") (name "Net-(PWR-C)") (class "Default")
      (node (ref "PWR") (pin "1") (pinfunction "C_1") (pintype "passive"))
      (node (ref "R2") (pin "2") (pinfunction "2_2") (pintype "passive"))
    )
    (net (code "62") (name "Net-(Q1-D)") (class "Default")
      (node (ref "BATT1") (pin "2") (pinfunction "2_2") (pintype "passive"))
      (node (ref "Q1") (pin "2") (pinfunction "D_2") (pintype "passive"))
    )
    (net (code "63") (name "Net-(Q1-G)") (class "Default")
      (node (ref "BATT1") (pin "1") (pinfunction "1_1") (pintype "passive"))
      (node (ref "C11") (pin "1") (pinfunction "1_1") (pintype "passive"))
      (node (ref "Q1") (pin "1") (pinfunction "G_1") (pintype "passive"))
      (node (ref "U2") (pin "2") (pinfunction "BAT_2") (pintype "power_in"))
      (node (ref "U2") (pin "3") (pinfunction "BAT_3") (pintype "power_in"))
    )
    (net (code "64") (name "Net-(Q2-S)") (class "Default")
      (node (ref "MOTOR") (pin "3") (pinfunction "3_3") (pintype "passive"))
      (node (ref "Q2") (pin "2") (pinfunction "S_2") (pintype "passive"))
    )
    (net (code "65") (name "Net-(RGB1-Blue_C)") (class "Default")
      (node (ref "R11") (pin "2") (pinfunction "2_2") (pintype "passive"))
      (node (ref "RGB1") (pin "3") (pinfunction "Blue_C_3") (pintype "passive"))
    )
    (net (code "66") (name "Net-(RGB1-Green_C)") (class "Default")
      (node (ref "R10") (pin "2") (pinfunction "2_2") (pintype "passive"))
      (node (ref "RGB1") (pin "4") (pinfunction "Green_C_4") (pintype "passive"))
    )
    (net (code "67") (name "Net-(RGB1-Red_C)") (class "Default")
      (node (ref "R12") (pin "2") (pinfunction "2_2") (pintype "passive"))
      (node (ref "RGB1") (pin "2") (pinfunction "Red_C_2") (pintype "passive"))
    )
    (net (code "68") (name "Net-(U1-L)") (class "Default")
      (node (ref "L1") (pin "2") (pinfunction "2_2") (pintype "passive"))
      (node (ref "U1") (pin "5") (pinfunction "L_5") (pintype "power_in"))
    )
    (net (code "69") (name "Net-(U2-ILIM)") (class "Default")
      (node (ref "R1") (pin "1") (pinfunction "1_1") (pintype "passive"))
      (node (ref "U2") (pin "12") (pinfunction "ILIM_12") (pintype "input"))
    )
    (net (code "70") (name "Net-(U2-ISET)") (class "Default")
      (node (ref "R5") (pin "2") (pinfunction "2_2") (pintype "passive"))
      (node (ref "U2") (pin "16") (pinfunction "ISET_16") (pintype "input"))
    )
    (net (code "71") (name "Net-(U2-TS)") (class "Default")
      (node (ref "R6") (pin "2") (pinfunction "2_2") (pintype "passive"))
      (node (ref "U2") (pin "1") (pinfunction "TS_1") (pintype "input"))
    )
    (net (code "72") (name "Net-(U3-EN)") (class "Default")
      (node (ref "C10") (pin "2") (pinfunction "2_2") (pintype "passive"))
      (node (ref "U3") (pin "6") (pinfunction "EN_6") (pintype "input"))
      (node (ref "U3") (pin "7") (pinfunction "PS/SYNC_7") (pintype "input"))
      (node (ref "U3") (pin "8") (pinfunction "VINA_8") (pintype "power_in"))
    )
    (net (code "73") (name "Net-(U3-FB)") (class "Default")
      (node (ref "R7") (pin "1") (pinfunction "1_1") (pintype "passive"))
      (node (ref "R8") (pin "2") (pinfunction "2_2") (pintype "passive"))
      (node (ref "U3") (pin "10") (pinfunction "FB_10") (pintype "input"))
    )
    (net (code "74") (name "Net-(U3-L1)") (class "Default")
      (node (ref "L2") (pin "1") (pinfunction "1_1") (pintype "passive"))
      (node (ref "U3") (pin "4") (pinfunction "L1_4") (pintype "passive"))
    )
    (net (code "75") (name "Net-(U3-L2)") (class "Default")
      (node (ref "L2") (pin "2") (pinfunction "2_2") (pintype "passive"))
      (node (ref "U3") (pin "2") (pinfunction "L2_2") (pintype "passive"))
    )
    (net (code "76") (name "Net-(U4-PC13)") (class "Default")
      (node (ref "OSC") (pin "1") (pinfunction "1_1") (pintype "passive"))
      (node (ref "U4") (pin "2") (pinfunction "PC13_2") (pintype "bidirectional"))
    )
    (net (code "77") (name "Net-(U4-PH0-OSC_IN(PH0))") (class "Default")
      (node (ref "C21") (pin "2") (pinfunction "2_2") (pintype "passive"))
      (node (ref "U4") (pin "5") (pinfunction "PH0-OSC_IN(PH0)_5") (pintype "bidirectional"))
      (node (ref "Y1") (pin "1") (pinfunction "1_1") (pintype "passive"))
    )
    (net (code "78") (name "Net-(U4-PH1-OSC_OUT(PH1))") (class "Default")
      (node (ref "C22") (pin "1") (pinfunction "1_1") (pintype "passive"))
      (node (ref "U4") (pin "6") (pinfunction "PH1-OSC_OUT(PH1)_6") (pintype "bidirectional"))
      (node (ref "Y1") (pin "3") (pinfunction "3_3") (pintype "passive"))
    )
    (net (code "79") (name "Net-(U5-CANH)") (class "Default")
      (node (ref "J3") (pin "1") (pinfunction "1_1") (pintype "passive"))
      (node (ref "MOTOR") (pin "1") (pinfunction "1_1") (pintype "passive"))
      (node (ref "U5") (pin "7") (pinfunction "CANH_7") (pintype "bidirectional"))
    )
    (net (code "80") (name "Net-(U5-CANL)") (class "Default")
      (node (ref "MOTOR") (pin "2") (pinfunction "2_2") (pintype "passive"))
      (node (ref "R22") (pin "2") (pinfunction "2_2") (pintype "passive"))
      (node (ref "U5") (pin "6") (pinfunction "CANL_6") (pintype "bidirectional"))
    )
    (net (code "81") (name "V3.3") (class "Default")
      (node (ref "C12") (pin "1") (pinfunction "1_1") (pintype "passive"))
      (node (ref "C13") (pin "1") (pinfunction "1_1") (pintype "passive"))
      (node (ref "C14") (pin "1") (pinfunction "1_1") (pintype "passive"))
      (node (ref "C15") (pin "1") (pinfunction "1_1") (pintype "passive"))
      (node (ref "C16") (pin "1") (pinfunction "1_1") (pintype "passive"))
      (node (ref "C17") (pin "1") (pinfunction "1_1") (pintype "passive"))
      (node (ref "C18") (pin "1") (pinfunction "1_1") (pintype "passive"))
      (node (ref "C23") (pin "1") (pinfunction "1_1") (pintype "passive"))
      (node (ref "C24") (pin "1") (pinfunction "1_1") (pintype "passive"))
      (node (ref "C25") (pin "1") (pinfunction "1_1") (pintype "passive"))
      (node (ref "C28") (pin "1") (pinfunction "1_1") (pintype "passive"))
      (node (ref "C29") (pin "1") (pinfunction "1_1") (pintype "passive"))
      (node (ref "C6") (pin "1") (pinfunction "1_1") (pintype "passive"))
      (node (ref "C8") (pin "1") (pinfunction "1_1") (pintype "passive"))
      (node (ref "C9") (pin "1") (pinfunction "1_1") (pintype "passive"))
      (node (ref "ENC1") (pin "1") (pinfunction "1_1") (pintype "passive"))
      (node (ref "ENC2") (pin "1") (pinfunction "1_1") (pintype "passive"))
      (node (ref "IMU1") (pin "1") (pinfunction "1_1") (pintype "passive"))
      (node (ref "IMU2") (pin "1") (pinfunction "1_1") (pintype "passive"))
      (node (ref "J1") (pin "4") (pinfunction "VDD_4") (pintype "power_in"))
      (node (ref "PROG") (pin "1") (pinfunction "1_1") (pintype "passive"))
      (node (ref "R7") (pin "2") (pinfunction "2_2") (pintype "passive"))
      (node (ref "RGB1") (pin "1") (pinfunction "Common_Anode_1") (pintype "passive"))
      (node (ref "U3") (pin "1") (pinfunction "VOUT_1") (pintype "power_in"))
      (node (ref "U4") (pin "13") (pinfunction "VDDA/VREF+_13") (pintype "power_in"))
      (node (ref "U4") (pin "19") (pinfunction "VDD_19") (pintype "power_in"))
      (node (ref "U4") (pin "32") (pinfunction "VDD_32") (pintype "power_in"))
      (node (ref "U4") (pin "48") (pinfunction "VDDUSB_48") (pintype "power_in"))
      (node (ref "U4") (pin "64") (pinfunction "VDD_64") (pintype "power_in"))
      (node (ref "U5") (pin "3") (pinfunction "VCC_3") (pintype "power_in"))
      (node (ref "U5") (pin "8") (pinfunction "RS_8") (pintype "input"))
    )
    (net (code "82") (name "V5") (class "Default")
      (node (ref "C2") (pin "1") (pinfunction "1_1") (pintype "passive"))
      (node (ref "C26") (pin "1") (pinfunction "1_1") (pintype "passive"))
      (node (ref "C27") (pin "1") (pinfunction "1_1") (pintype "passive"))
      (node (ref "LC1") (pin "1") (pinfunction "1_1") (pintype "passive"))
      (node (ref "LC2") (pin "1") (pinfunction "1_1") (pintype "passive"))
      (node (ref "PWR") (pin "2") (pinfunction "A_2") (pintype "passive"))
      (node (ref "Q2") (pin "3") (pinfunction "D_3") (pintype "passive"))
      (node (ref "U1") (pin "2") (pinfunction "FB_2") (pintype "input"))
      (node (ref "U1") (pin "4") (pinfunction "VOUT_4") (pintype "power_in"))
    )
    (net (code "83") (name "Vsys") (class "Default")
      (node (ref "C1") (pin "1") (pinfunction "1_1") (pintype "passive"))
      (node (ref "C7") (pin "1") (pinfunction "1_1") (pintype "passive"))
      (node (ref "L1") (pin "1") (pinfunction "1_1") (pintype "passive"))
      (node (ref "ON1") (pin "2") (pinfunction "COM_2") (pintype "passive"))
      (node (ref "U1") (pin "1") (pinfunction "VIN_1") (pintype "power_in"))
      (node (ref "U3") (pin "5") (pinfunction "VIN_5") (pintype "power_in"))
    )
    (net (code "84") (name "Vusb") (class "Default")
      (node (ref "C20") (pin "1") (pinfunction "1_1") (pintype "passive"))
      (node (ref "C3") (pin "1") (pinfunction "1_1") (pintype "passive"))
      (node (ref "J2") (pin "A4") (pinfunction "VBUS_A4") (pintype "passive"))
      (node (ref "J2") (pin "A9") (pinfunction "VBUS_A9") (pintype "passive"))
      (node (ref "J2") (pin "B4") (pinfunction "VBUS_B4") (pintype "passive"))
      (node (ref "J2") (pin "B9") (pinfunction "VBUS_B9") (pintype "passive"))
      (node (ref "ON1") (pin "3") (pinfunction "3_3") (pintype "passive"))
      (node (ref "U2") (pin "13") (pinfunction "IN_13") (pintype "power_in"))
      (node (ref "U4") (pin "42") (pinfunction "PA9_42") (pintype "bidirectional"))
    )
    (net (code "85") (name "unconnected-(J2A-SBU1-PadA8)") (class "Default")
      (node (ref "J2") (pin "A8") (pinfunction "SBU1_A8") (pintype "passive"))
    )
    (net (code "86") (name "unconnected-(J2B-SBU2-PadB8)") (class "Default")
      (node (ref "J2") (pin "B8") (pinfunction "SBU2_B8") (pintype "passive"))
    )
    (net (code "87") (name "unconnected-(U2-ITERM-Pad15)") (class "Default")
      (node (ref "U2") (pin "15") (pinfunction "ITERM_15") (pintype "input+no_connect"))
    )
    (net (code "88") (name "unconnected-(U2-TMR-Pad14)") (class "Default")
      (node (ref "U2") (pin "14") (pinfunction "TMR_14") (pintype "input+no_connect"))
    )
    (net (code "89") (name "unconnected-(U4-VBAT-Pad1)") (class "Default")
      (node (ref "U4") (pin "1") (pinfunction "VBAT_1") (pintype "power_in"))
    )
    (net (code "90") (name "unconnected-(U5-VREF-Pad5)") (class "Default")
      (node (ref "U5") (pin "5") (pinfunction "VREF_5") (pintype "output"))
    )
  )
)
